# Saldatore.net
KiCad netlist of a schematic drawn in EAGLE
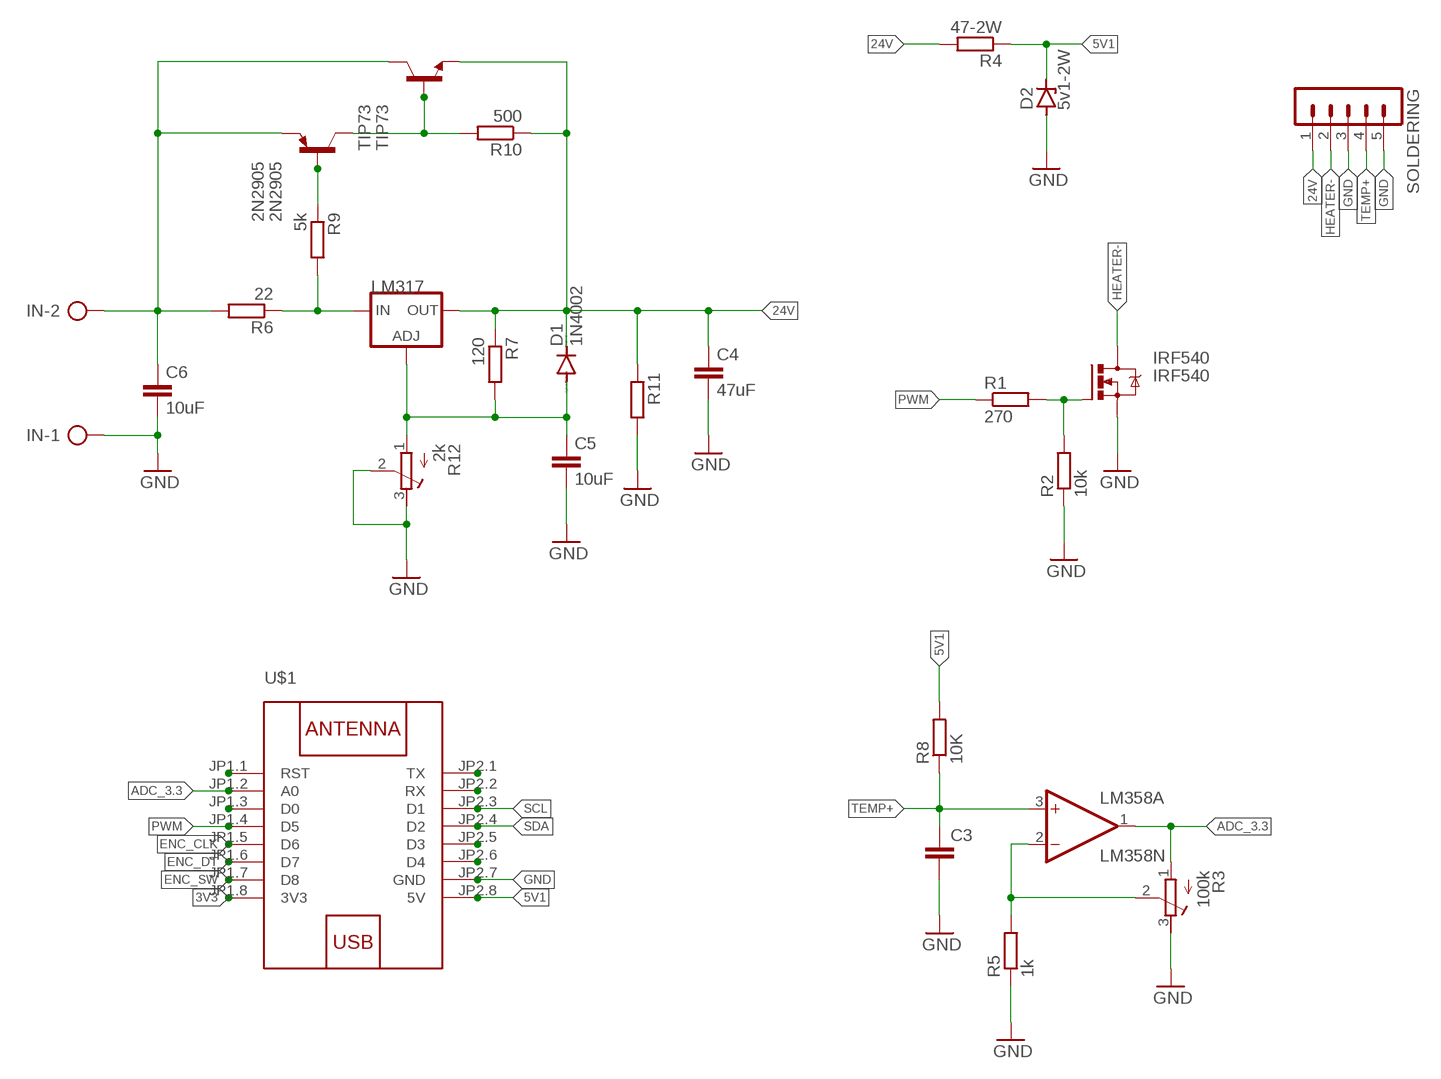
[diagram p0: schematic, sheet 1]

(export (version "E")
  (design (tool "Eeschema 10.0.6"))
  (components
    (comp (ref "2N2905")
      (value "2N2905")
      (footprint "eagle-import:TO39")
      (libsource (lib "eagle-import") (part "2N2905"))
    )
    (comp (ref "C3")
      (value "C-EU025-025X050")
      (footprint "eagle-import:C025-025X050")
      (libsource (lib "eagle-import") (part "C-EU025-025X050"))
    )
    (comp (ref "C4")
      (value "47uF")
      (footprint "eagle-import:C025-025X050")
      (libsource (lib "eagle-import") (part "C-EU025-025X050"))
    )
    (comp (ref "C5")
      (value "10uF")
      (footprint "eagle-import:C025-025X050")
      (libsource (lib "eagle-import") (part "C-EU025-025X050"))
    )
    (comp (ref "C6")
      (value "10uF")
      (footprint "eagle-import:C025-025X050")
      (libsource (lib "eagle-import") (part "C-EU025-025X050"))
    )
    (comp (ref "D1")
      (value "1N4002")
      (footprint "eagle-import:DIOAD860W70L460D235B")
      (libsource (lib "eagle-import") (part "1N4004DO-41"))
    )
    (comp (ref "D2")
      (value "5v1-2W")
      (footprint "eagle-import:DO41Z10")
      (libsource (lib "eagle-import") (part "ZENER-DIODEDO41Z10"))
    )
    (comp (ref "IN")
      (value "SMKDSP_1,5/2")
      (footprint "eagle-import:SMKDSP_1,5_2")
      (fields (field (name "MF") "FARNELL") (field (name "MPN") "1733570"))
      (libsource (lib "eagle-import") (part "SMKDSP_1,5/2"))
    )
    (comp (ref "IRF540")
      (value "IRF540")
      (footprint "eagle-import:TO220BV")
      (libsource (lib "eagle-import") (part "IRF540"))
    )
    (comp (ref "LM317")
      (value "LM317TS317TS_TO220")
      (footprint "eagle-import:TO220V")
      (libsource (lib "eagle-import") (part "LM317TS317TS_TO220"))
    )
    (comp (ref "LM358")
      (value "LM358N")
      (footprint "eagle-import:DIL08")
      (libsource (lib "eagle-import") (part "LM358N"))
    )
    (comp (ref "R1")
      (value "270")
      (footprint "eagle-import:0204_7")
      (libsource (lib "eagle-import") (part "R-EU_0204/7"))
    )
    (comp (ref "R2")
      (value "10k")
      (footprint "eagle-import:0204_7")
      (libsource (lib "eagle-import") (part "R-EU_0204/7"))
    )
    (comp (ref "R3")
      (value "100k")
      (footprint "eagle-import:RTRIM64W")
      (libsource (lib "eagle-import") (part "R-TRIMM64W"))
    )
    (comp (ref "R4")
      (value "47-2W")
      (footprint "eagle-import:0204_7")
      (libsource (lib "eagle-import") (part "R-EU_0204/7"))
    )
    (comp (ref "R5")
      (value "1k")
      (footprint "eagle-import:0204_7")
      (libsource (lib "eagle-import") (part "R-EU_0204/7"))
    )
    (comp (ref "R6")
      (value "22")
      (footprint "eagle-import:0204_7")
      (libsource (lib "eagle-import") (part "R-EU_0204/7"))
    )
    (comp (ref "R7")
      (value "120")
      (footprint "eagle-import:0204_7")
      (libsource (lib "eagle-import") (part "R-EU_0204/7"))
    )
    (comp (ref "R8")
      (value "10K")
      (footprint "eagle-import:0204_7")
      (libsource (lib "eagle-import") (part "R-EU_0204/7"))
    )
    (comp (ref "R9")
      (value "5k")
      (footprint "eagle-import:0204_7")
      (libsource (lib "eagle-import") (part "R-EU_0204/7"))
    )
    (comp (ref "R10")
      (value "500")
      (footprint "eagle-import:0204_7")
      (libsource (lib "eagle-import") (part "R-EU_0204/7"))
    )
    (comp (ref "R11")
      (value "R-EU_0204/7")
      (footprint "eagle-import:0204_7")
      (libsource (lib "eagle-import") (part "R-EU_0204/7"))
    )
    (comp (ref "R12")
      (value "2k")
      (footprint "eagle-import:RTRIM64W")
      (libsource (lib "eagle-import") (part "R-TRIMM64W"))
    )
    (comp (ref "SOLDERING")
      (value "MA05-1")
      (footprint "eagle-import:MA05-1")
      (libsource (lib "eagle-import") (part "MA05-1"))
    )
    (comp (ref "TIP73")
      (value "TIP73")
      (footprint "eagle-import:TO5")
      (libsource (lib "eagle-import") (part "2N1613"))
    )
    (comp (ref "U$1")
      (value "WEMOS-D1-MINI")
      (footprint "eagle-import:WEMOS-D1-MINI")
      (libsource (lib "eagle-import") (part "WEMOS-D1-MINI"))
    )
  )
  (nets
    (net (code "1") (name "3V3") (class "Default")
      (node (ref "U$1") (pin "JP1.8") (pinfunction "3V3_JP1.8") (pintype "power_in"))
    )
    (net (code "2") (name "5V1") (class "Default")
      (node (ref "D2") (pin "C") (pinfunction "C_C") (pintype "passive"))
      (node (ref "R4") (pin "1") (pinfunction "1_1") (pintype "passive"))
      (node (ref "R8") (pin "2") (pinfunction "2_2") (pintype "passive"))
      (node (ref "U$1") (pin "JP2.8") (pinfunction "5V_JP2.8") (pintype "power_in"))
    )
    (net (code "3") (name "24V") (class "Default")
      (node (ref "C4") (pin "1") (pinfunction "1_1") (pintype "passive"))
      (node (ref "D1") (pin "1") (pinfunction "C_1") (pintype "passive"))
      (node (ref "LM317") (pin "2") (pinfunction "OUT_2") (pintype "passive"))
      (node (ref "R10") (pin "1") (pinfunction "1_1") (pintype "passive"))
      (node (ref "R11") (pin "1") (pinfunction "1_1") (pintype "passive"))
      (node (ref "R4") (pin "2") (pinfunction "2_2") (pintype "passive"))
      (node (ref "R7") (pin "1") (pinfunction "1_1") (pintype "passive"))
      (node (ref "SOLDERING") (pin "1") (pinfunction "1_1") (pintype "passive"))
      (node (ref "TIP73") (pin "1") (pinfunction "E_1") (pintype "passive"))
    )
    (net (code "4") (name "ADC_3.3") (class "Default")
      (node (ref "LM358") (pin "1") (pinfunction "OUT_1") (pintype "output"))
      (node (ref "R3") (pin "1") (pinfunction "A_1") (pintype "passive"))
      (node (ref "U$1") (pin "JP1.2") (pinfunction "A0_JP1.2") (pintype "bidirectional"))
    )
    (net (code "5") (name "ENC_CLK") (class "Default")
      (node (ref "U$1") (pin "JP1.5") (pinfunction "D6_JP1.5") (pintype "bidirectional"))
    )
    (net (code "6") (name "ENC_DT") (class "Default")
      (node (ref "U$1") (pin "JP1.6") (pinfunction "D7_JP1.6") (pintype "bidirectional"))
    )
    (net (code "7") (name "ENC_SW") (class "Default")
      (node (ref "U$1") (pin "JP1.7") (pinfunction "D8_JP1.7") (pintype "bidirectional"))
    )
    (net (code "8") (name "GND") (class "Default")
      (node (ref "C3") (pin "2") (pinfunction "2_2") (pintype "passive"))
      (node (ref "C4") (pin "2") (pinfunction "2_2") (pintype "passive"))
      (node (ref "C5") (pin "2") (pinfunction "2_2") (pintype "passive"))
      (node (ref "C6") (pin "2") (pinfunction "2_2") (pintype "passive"))
      (node (ref "D2") (pin "A") (pinfunction "A_A") (pintype "passive"))
      (node (ref "IN") (pin "1") (pinfunction "KL_1") (pintype "passive"))
      (node (ref "IRF540") (pin "S") (pinfunction "S_S") (pintype "passive"))
      (node (ref "R11") (pin "2") (pinfunction "2_2") (pintype "passive"))
      (node (ref "R12") (pin "2") (pinfunction "S_2") (pintype "passive"))
      (node (ref "R12") (pin "3") (pinfunction "E_3") (pintype "passive"))
      (node (ref "R2") (pin "1") (pinfunction "1_1") (pintype "passive"))
      (node (ref "R3") (pin "3") (pinfunction "E_3") (pintype "passive"))
      (node (ref "R5") (pin "1") (pinfunction "1_1") (pintype "passive"))
      (node (ref "SOLDERING") (pin "3") (pinfunction "3_3") (pintype "passive"))
      (node (ref "SOLDERING") (pin "5") (pinfunction "5_5") (pintype "passive"))
      (node (ref "U$1") (pin "JP2.7") (pinfunction "GND_JP2.7") (pintype "power_in"))
    )
    (net (code "9") (name "HEATER-") (class "Default")
      (node (ref "IRF540") (pin "D") (pinfunction "D_D") (pintype "passive"))
      (node (ref "SOLDERING") (pin "2") (pinfunction "2_2") (pintype "passive"))
    )
    (net (code "10") (name "Net-(2N2905-B)") (class "Default")
      (node (ref "2N2905") (pin "2") (pinfunction "B_2") (pintype "passive"))
      (node (ref "R9") (pin "1") (pinfunction "1_1") (pintype "passive"))
    )
    (net (code "11") (name "Net-(2N2905-C)") (class "Default")
      (node (ref "2N2905") (pin "3") (pinfunction "C_3") (pintype "passive"))
      (node (ref "R10") (pin "2") (pinfunction "2_2") (pintype "passive"))
      (node (ref "TIP73") (pin "2") (pinfunction "B_2") (pintype "passive"))
    )
    (net (code "12") (name "Net-(2N2905-E)") (class "Default")
      (node (ref "2N2905") (pin "1") (pinfunction "E_1") (pintype "passive"))
      (node (ref "C6") (pin "1") (pinfunction "1_1") (pintype "passive"))
      (node (ref "IN") (pin "2") (pinfunction "KL_2") (pintype "passive"))
      (node (ref "R6") (pin "2") (pinfunction "2_2") (pintype "passive"))
      (node (ref "TIP73") (pin "3") (pinfunction "C_3") (pintype "passive"))
    )
    (net (code "13") (name "Net-(D1-A)") (class "Default")
      (node (ref "C5") (pin "1") (pinfunction "1_1") (pintype "passive"))
      (node (ref "D1") (pin "2") (pinfunction "A_2") (pintype "passive"))
      (node (ref "LM317") (pin "1") (pinfunction "ADJ_1") (pintype "input"))
      (node (ref "R12") (pin "1") (pinfunction "A_1") (pintype "passive"))
      (node (ref "R7") (pin "2") (pinfunction "2_2") (pintype "passive"))
    )
    (net (code "14") (name "Net-(IRF540-PadG)") (class "Default")
      (node (ref "IRF540") (pin "G") (pinfunction "G_G") (pintype "passive"))
      (node (ref "R1") (pin "2") (pinfunction "2_2") (pintype "passive"))
      (node (ref "R2") (pin "2") (pinfunction "2_2") (pintype "passive"))
    )
    (net (code "15") (name "Net-(LM317-IN)") (class "Default")
      (node (ref "LM317") (pin "3") (pinfunction "IN_3") (pintype "input"))
      (node (ref "R6") (pin "1") (pinfunction "1_1") (pintype "passive"))
      (node (ref "R9") (pin "2") (pinfunction "2_2") (pintype "passive"))
    )
    (net (code "16") (name "Net-(LM358A--IN)") (class "Default")
      (node (ref "LM358") (pin "2") (pinfunction "-IN_2") (pintype "input"))
      (node (ref "R3") (pin "2") (pinfunction "S_2") (pintype "passive"))
      (node (ref "R5") (pin "2") (pinfunction "2_2") (pintype "passive"))
    )
    (net (code "17") (name "PWM") (class "Default")
      (node (ref "R1") (pin "1") (pinfunction "1_1") (pintype "passive"))
      (node (ref "U$1") (pin "JP1.4") (pinfunction "D5_JP1.4") (pintype "bidirectional"))
    )
    (net (code "18") (name "SCL") (class "Default")
      (node (ref "U$1") (pin "JP2.3") (pinfunction "D1_JP2.3") (pintype "bidirectional"))
    )
    (net (code "19") (name "SDA") (class "Default")
      (node (ref "U$1") (pin "JP2.4") (pinfunction "D2_JP2.4") (pintype "bidirectional"))
    )
    (net (code "20") (name "TEMP+") (class "Default")
      (node (ref "C3") (pin "1") (pinfunction "1_1") (pintype "passive"))
      (node (ref "LM358") (pin "3") (pinfunction "+IN_3") (pintype "input"))
      (node (ref "R8") (pin "1") (pinfunction "1_1") (pintype "passive"))
      (node (ref "SOLDERING") (pin "4") (pinfunction "4_4") (pintype "passive"))
    )
    (net (code "21") (name "unconnected-(U$1-D0-PadJP1.3)") (class "Default")
      (node (ref "U$1") (pin "JP1.3") (pinfunction "D0_JP1.3") (pintype "bidirectional"))
    )
    (net (code "22") (name "unconnected-(U$1-D3-PadJP2.5)") (class "Default")
      (node (ref "U$1") (pin "JP2.5") (pinfunction "D3_JP2.5") (pintype "bidirectional"))
    )
    (net (code "23") (name "unconnected-(U$1-D4-PadJP2.6)") (class "Default")
      (node (ref "U$1") (pin "JP2.6") (pinfunction "D4_JP2.6") (pintype "bidirectional"))
    )
    (net (code "24") (name "unconnected-(U$1-RST-PadJP1.1)") (class "Default")
      (node (ref "U$1") (pin "JP1.1") (pinfunction "RST_JP1.1") (pintype "bidirectional"))
    )
    (net (code "25") (name "unconnected-(U$1-RX-PadJP2.2)") (class "Default")
      (node (ref "U$1") (pin "JP2.2") (pinfunction "RX_JP2.2") (pintype "bidirectional"))
    )
    (net (code "26") (name "unconnected-(U$1-TX-PadJP2.1)") (class "Default")
      (node (ref "U$1") (pin "JP2.1") (pinfunction "TX_JP2.1") (pintype "bidirectional"))
    )
  )
)
